# 5_High_Voltage.net
KiCad netlist of a schematic drawn in Altium Designer
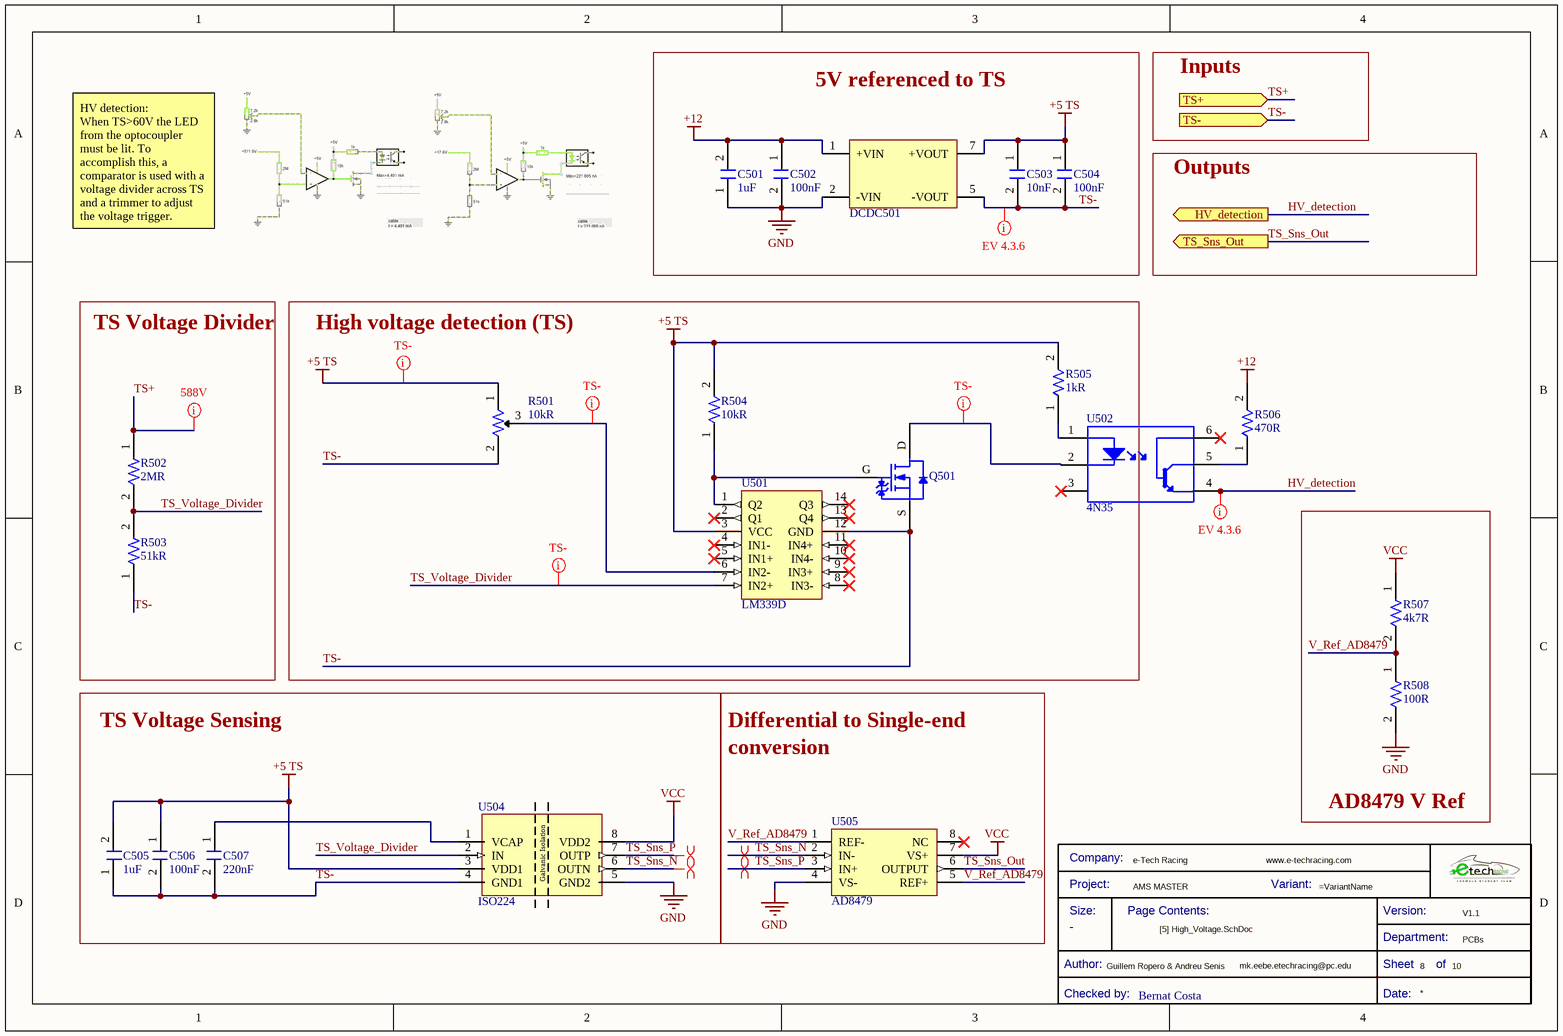
[diagram p0: [5] High_Voltage.SchDoc]

(export (version "E")
  (design (tool "Eeschema 10.0.6"))
  (components
    (comp (ref "C501")
      (value "885012207103")
      (footprint "C0805FNPC-R")
      (fields
        (field (name "TOLERANCE") "10%")
        (field (name "CAPACITANCE") "1uF")
        (field (name ".CREATOR") "GP")
      )
      (libsource (lib "Passives") (part "C1u-50V-0805FNPC-X7R"))
    )
    (comp (ref "C502")
      (value "885012207098")
      (footprint "C0805FNPC-R")
      (description "Cap, 0.1ΜF, 50V, 10%, X7R, 0805")
      (fields
        (field (name "TOLERANCE") "10%")
        (field (name "CAPACITANCE") "100nF")
        (field (name ".CREATOR") "DR")
      )
      (libsource (lib "Passives") (part "C100n-50V-0805FNPC-X7R"))
    )
    (comp (ref "C503")
      (value "885012207092")
      (footprint "C0805FNPC-R")
      (description "Cap, 0.01ΜF, 50V, 10%, X7R, 0805")
      (fields
        (field (name "TOLERANCE") "10%")
        (field (name "CAPACITANCE") "10nF")
        (field (name ".CREATOR") "DR")
      )
      (libsource (lib "Passives") (part "C10n-50V-0805FNPC-X7R"))
    )
    (comp (ref "C504")
      (value "885012207098")
      (footprint "C0805FNPC-R")
      (description "Cap, 0.1ΜF, 50V, 10%, X7R, 0805")
      (fields
        (field (name "TOLERANCE") "10%")
        (field (name "CAPACITANCE") "100nF")
        (field (name ".CREATOR") "DR")
      )
      (libsource (lib "Passives") (part "C100n-50V-0805FNPC-X7R"))
    )
    (comp (ref "C505")
      (value "885012207103")
      (footprint "C0805FNPC-R")
      (fields
        (field (name "TOLERANCE") "10%")
        (field (name "CAPACITANCE") "1uF")
        (field (name ".CREATOR") "GP")
      )
      (libsource (lib "Passives") (part "C1u-50V-0805FNPC-X7R"))
    )
    (comp (ref "C506")
      (value "885012207098")
      (footprint "C0805FNPC-R")
      (description "Cap, 0.1ΜF, 50V, 10%, X7R, 0805")
      (fields
        (field (name "TOLERANCE") "10%")
        (field (name "CAPACITANCE") "100nF")
        (field (name ".CREATOR") "DR")
      )
      (libsource (lib "Passives") (part "C100n-50V-0805FNPC-X7R"))
    )
    (comp (ref "C507")
      (value "885012208058")
      (footprint "C0805FNPC-W")
      (description "Cap Ceramic 0.22uF 50V X5R 10% Pad SMD 0805 85C Low ESR Automotive T/R")
      (fields
        (field (name "MANUFACTURER") "Taiyo Yuden")
        (field (name "MANUFACTURER PART NUMBER") "UMK212BJ224KGHT")
        (field (name "CAPACITANCE") "220nF")
        (field (name ".CREATOR") "DR")
      )
      (libsource (lib "Passives") (part "C0.22u-0805FNPC-X5R"))
    )
    (comp (ref "DCDC501")
      (value "1779405241")
      (footprint "DCDC2W-ISO/1779405X41")
      (description "WPME-FISM Fixed Isolated Module, SIP-7, 10.8-13.2Vin, 5Vout")
      (fields (field (name "MANUFACTURER") "Wurth Elektronik"))
      (libsource (lib "Semiconductor") (part "DCDC-ISO-2W/12V/5V"))
    )
    (comp (ref "Q501")
      (value "SQ2318BES-T1_GE3")
      (footprint "TRT-NCH-3/35-CPH")
      (description "Automotive N-channel 40 V (d-s) 175C Mosfet SOT-23")
      (fields (field (name ".CREATOR") "DO"))
      (libsource (lib "Semiconductor") (part "TRT-NCH-8/40-SQ"))
    )
    (comp (ref "R501")
      (value "3296W-1-103LF")
      (footprint "R10k-VTR")
      (description "Trimmer, Cermet, Rest 10 Kilohms, PCB, 25 Turns, Pwr-Rtg 0.5W, 3296 Series")
      (fields
        (field (name "MANUFACTURER") "Bourns")
        (field (name "TOLERANCE") "10%")
        (field (name "RESISTANCE") "10kR")
        (field (name ".CREATOR") "DO")
      )
      (libsource (lib "Passives") (part "R10k-VTR"))
    )
    (comp (ref "R502")
      (value "R2M-2512FTK")
      (footprint "R2512FTK")
      (description "Current Sense Resistors - SMD 3watts .002ohms 1%")
      (fields
        (field (name "MANUFACTURER") "Vishay Dale")
        (field (name "MANUFACTURER PART NUMBER") "WSLP25122L000FEA")
        (field (name "RESISTANCE") "2MR")
      )
      (libsource (lib "Passives") (part "R2M-2512FTK"))
    )
    (comp (ref "R503")
      (value "CRCW120610K0FKEA")
      (footprint "R1206FTK-W")
      (description "Res Thick Film 1206 51K Ohm 1% 1/4W ±100ppm/°C Molded SMD SMD Punched Carrier T/R")
      (fields
        (field (name "MANUFACTURER") "Panasonic")
        (field (name "MANUFACTURER PART NUMBER") "ERJ-S08F5102V")
        (field (name "RESISTANCE") "51kR")
        (field (name ".CREATOR") "DO")
      )
      (libsource (lib "Passives") (part "R51k-1206FTK"))
    )
    (comp (ref "R504")
      (value "CR0805-JW-103ELF")
      (footprint "R0805FTK")
      (fields
        (field (name "TOLERANCE") "5%")
        (field (name "RESISTANCE") "10kR")
        (field (name ".CREATOR") "DR")
      )
      (libsource (lib "Passives") (part "R10k-0805FTK"))
    )
    (comp (ref "R505")
      (value "CR0805-JW-102ELF")
      (footprint "R0805FTK")
      (description "Res Thick Film 0805 1K Ohm 5% 1/8W ±200ppm/°C Molded SMD SMD Paper Tape on Plastic Reel")
      (fields
        (field (name "TOLERANCE") "5%")
        (field (name "RESISTANCE") "1kR")
        (field (name ".CREATOR") "GP")
      )
      (libsource (lib "Passives") (part "R1k-0805FTK"))
    )
    (comp (ref "R506")
      (value "CR0805-FX-4700GLF")
      (footprint "R0805FTK")
      (description "Res Thick Film 0805 470 Ohm 1% 1/8W ±100ppm/°C Molded SMD SMD Paper Tape on Plastic Reel")
      (fields
        (field (name "TOLERANCE") "1%")
        (field (name "RESISTANCE") "470R")
        (field (name ".CREATOR") "DR")
      )
      (libsource (lib "Passives") (part "R470-0805FTK"))
    )
    (comp (ref "R507")
      (value "CR0805-JW-472ELF")
      (footprint "R0805FTK")
      (description "Res Thick Film 0805 4.7K Ohm 5% 1/8W ±200ppm/°C Molded SMD SMD Paper Tape on Plastic Reel")
      (fields
        (field (name "TOLERANCE") "5%")
        (field (name "RESISTANCE") "4k7R")
        (field (name ".CREATOR") "DR")
      )
      (libsource (lib "Passives") (part "R4.7K-0805FTK"))
    )
    (comp (ref "R508")
      (value "CR0805-FX-1000ELF")
      (footprint "R0805FTK")
      (description "Res Thick Film 0805 100 Ohm 1% 1/8W ±100ppm/°C Molded SMD SMD Paper Tape on Plastic Reel")
      (fields
        (field (name "TOLERANCE") "1%")
        (field (name "RESISTANCE") "100R")
        (field (name ".CREATOR") "DR")
      )
      (libsource (lib "Passives") (part "R100-0805FTK"))
    )
    (comp (ref "U501")
      (value "LM339D")
      (footprint "Array_4_Amp_LM339D")
      (description "Comparator Quad ±18V/36V 14-Pin SOIC Tube")
      (fields
        (field (name "MANUFACTURER") "Texas Instruments")
        (field (name "MANUFACTURER PART NUMBER") "LM339D")
        (field (name ".CREATOR") "DO")
      )
      (libsource (lib "Integrated circuits") (part "Array_4_Amp_LM339D"))
    )
    (comp (ref "U502")
      (value "4N35")
      (footprint "Optocoupler_4N35")
      (description "Optocoupler DC-IN 1-CH Transistor With Base DC-OUT 6-Pin PDIP SMD T/R")
      (fields
        (field (name "MANUFACTURER") "Vishay Lite-On")
        (field (name "MANUFACTURER PART NUMBER") "CNY17-4S-TA1")
        (field (name ".CREATOR") "DO")
      )
      (libsource (lib "Semiconductor") (part "Optocoupler_4N35"))
    )
    (comp (ref "U504")
      (value "ISO224")
      (footprint "SOIC, 8 Pin 1.27 mm, Body 10,90x3,90mm,")
      (libsource (lib "Integrated circuits") (part "ISO224"))
    )
    (comp (ref "U505")
      (value "AD8479")
      (footprint "SOIC127P600X175-8N")
      (description "±600 V common-mode Voltage range, Fixed gain of 1, \r\nWide power supply range of ±2.5 V to ±18 V.")
      (libsource (lib "Integrated circuits") (part "AD8479ARZ-RL"))
    )
  )
  (nets
    (net (code "1") (name "+5 TS") (class "Default")
      (node (ref "C503") (pin "1") (pinfunction "1_1") (pintype "passive"))
      (node (ref "C504") (pin "1") (pinfunction "1_1") (pintype "passive"))
      (node (ref "C505") (pin "2") (pinfunction "2_2") (pintype "passive"))
      (node (ref "C506") (pin "1") (pinfunction "1_1") (pintype "passive"))
      (node (ref "DCDC501") (pin "7") (pinfunction "+VOUT_7") (pintype "passive"))
      (node (ref "R501") (pin "1") (pinfunction "2_1") (pintype "passive"))
      (node (ref "R504") (pin "2") (pinfunction "2_2") (pintype "passive"))
      (node (ref "R505") (pin "2") (pinfunction "2_2") (pintype "passive"))
      (node (ref "U501") (pin "3") (pinfunction "VCC_3") (pintype "power_in"))
      (node (ref "U504") (pin "3") (pinfunction "VDD1_3") (pintype "power_in"))
    )
    (net (code "2") (name "+12") (class "Default")
      (node (ref "C501") (pin "2") (pinfunction "2_2") (pintype "passive"))
      (node (ref "C502") (pin "1") (pinfunction "1_1") (pintype "passive"))
      (node (ref "DCDC501") (pin "1") (pinfunction "+VIN_1") (pintype "passive"))
      (node (ref "R506") (pin "2") (pinfunction "2_2") (pintype "passive"))
    )
    (net (code "3") (name "/HV_detection") (class "Default")
      (node (ref "U502") (pin "4") (pinfunction "E_4") (pintype "passive"))
    )
    (net (code "4") (name "/TS+") (class "Default")
      (node (ref "R502") (pin "1") (pinfunction "1_1") (pintype "passive"))
    )
    (net (code "5") (name "/TS-") (class "Default")
      (node (ref "C503") (pin "2") (pinfunction "2_2") (pintype "passive"))
      (node (ref "C504") (pin "2") (pinfunction "2_2") (pintype "passive"))
      (node (ref "C505") (pin "1") (pinfunction "1_1") (pintype "passive"))
      (node (ref "C506") (pin "2") (pinfunction "2_2") (pintype "passive"))
      (node (ref "C507") (pin "2") (pinfunction "2_2") (pintype "passive"))
      (node (ref "DCDC501") (pin "5") (pinfunction "-VOUT_5") (pintype "passive"))
      (node (ref "Q501") (pin "S") (pinfunction "S_S") (pintype "passive"))
      (node (ref "R501") (pin "2") (pinfunction "2_2") (pintype "passive"))
      (node (ref "R503") (pin "1") (pinfunction "1_1") (pintype "passive"))
      (node (ref "U501") (pin "12") (pinfunction "GND_12") (pintype "power_in"))
      (node (ref "U504") (pin "4") (pinfunction "GND1_4") (pintype "passive"))
    )
    (net (code "6") (name "/TS_Sns_N") (class "Default")
      (node (ref "U504") (pin "6") (pinfunction "OUTN_6") (pintype "output"))
      (node (ref "U505") (pin "2") (pinfunction "IN-_2") (pintype "input"))
    )
    (net (code "7") (name "/TS_Sns_Out") (class "Default")
      (node (ref "U505") (pin "6") (pinfunction "OUTPUT_6") (pintype "output"))
    )
    (net (code "8") (name "/TS_Sns_P") (class "Default")
      (node (ref "U504") (pin "7") (pinfunction "OUTP_7") (pintype "output"))
      (node (ref "U505") (pin "3") (pinfunction "IN+_3") (pintype "input"))
    )
    (net (code "9") (name "/TS_Voltage_Divider") (class "Default")
      (node (ref "R502") (pin "2") (pinfunction "2_2") (pintype "passive"))
      (node (ref "R503") (pin "2") (pinfunction "2_2") (pintype "passive"))
      (node (ref "U501") (pin "7") (pinfunction "IN2+_7") (pintype "input"))
      (node (ref "U504") (pin "2") (pinfunction "IN_2") (pintype "input"))
    )
    (net (code "10") (name "/V_Ref_AD8479") (class "Default")
      (node (ref "R507") (pin "2") (pinfunction "2_2") (pintype "passive"))
      (node (ref "R508") (pin "1") (pinfunction "1_1") (pintype "passive"))
      (node (ref "U505") (pin "1") (pinfunction "REF-_1") (pintype "passive"))
      (node (ref "U505") (pin "5") (pinfunction "REF+_5") (pintype "passive"))
    )
    (net (code "11") (name "GND") (class "Default")
      (node (ref "C501") (pin "1") (pinfunction "1_1") (pintype "passive"))
      (node (ref "C502") (pin "2") (pinfunction "2_2") (pintype "passive"))
      (node (ref "DCDC501") (pin "2") (pinfunction "-VIN_2") (pintype "passive"))
      (node (ref "R508") (pin "2") (pinfunction "2_2") (pintype "passive"))
      (node (ref "U504") (pin "5") (pinfunction "GND2_5") (pintype "power_in"))
      (node (ref "U505") (pin "4") (pinfunction "VS-_4") (pintype "power_in"))
    )
    (net (code "12") (name "Net-(R506-Pad1)") (class "Default")
      (node (ref "R506") (pin "1") (pinfunction "1_1") (pintype "passive"))
      (node (ref "U502") (pin "5") (pinfunction "E_5") (pintype "passive"))
    )
    (net (code "13") (name "Net-(U501-IN2-)") (class "Default")
      (node (ref "R501") (pin "3") (pinfunction "3_3") (pintype "passive"))
      (node (ref "U501") (pin "6") (pinfunction "IN2-_6") (pintype "input"))
    )
    (net (code "14") (name "Net-(U501-Q2)") (class "Default")
      (node (ref "Q501") (pin "G") (pinfunction "G_G") (pintype "passive"))
      (node (ref "R504") (pin "1") (pinfunction "1_1") (pintype "passive"))
      (node (ref "U501") (pin "1") (pinfunction "Q2_1") (pintype "output"))
    )
    (net (code "15") (name "Net-(U502-A)") (class "Default")
      (node (ref "R505") (pin "1") (pinfunction "1_1") (pintype "passive"))
      (node (ref "U502") (pin "1") (pinfunction "A_1") (pintype "passive"))
    )
    (net (code "16") (name "Net-(U502-K)") (class "Default")
      (node (ref "Q501") (pin "D") (pinfunction "D_D") (pintype "passive"))
      (node (ref "U502") (pin "2") (pinfunction "K_2") (pintype "passive"))
    )
    (net (code "17") (name "Net-(U504-VCAP)") (class "Default")
      (node (ref "C507") (pin "1") (pinfunction "1_1") (pintype "passive"))
      (node (ref "U504") (pin "1") (pinfunction "VCAP_1") (pintype "passive"))
    )
    (net (code "18") (name "VCC") (class "Default")
      (node (ref "R507") (pin "1") (pinfunction "1_1") (pintype "passive"))
      (node (ref "U504") (pin "8") (pinfunction "VDD2_8") (pintype "power_in"))
      (node (ref "U505") (pin "7") (pinfunction "VS+_7") (pintype "power_in"))
    )
    (net (code "19") (name "unconnected-(U501-IN1+-Pad5)") (class "Default")
      (node (ref "U501") (pin "5") (pinfunction "IN1+_5") (pintype "input+no_connect"))
    )
    (net (code "20") (name "unconnected-(U501-IN1--Pad4)") (class "Default")
      (node (ref "U501") (pin "4") (pinfunction "IN1-_4") (pintype "input+no_connect"))
    )
    (net (code "21") (name "unconnected-(U501-IN3+-Pad9)") (class "Default")
      (node (ref "U501") (pin "9") (pinfunction "IN3+_9") (pintype "input+no_connect"))
    )
    (net (code "22") (name "unconnected-(U501-IN3--Pad8)") (class "Default")
      (node (ref "U501") (pin "8") (pinfunction "IN3-_8") (pintype "input+no_connect"))
    )
    (net (code "23") (name "unconnected-(U501-IN4+-Pad11)") (class "Default")
      (node (ref "U501") (pin "11") (pinfunction "IN4+_11") (pintype "input+no_connect"))
    )
    (net (code "24") (name "unconnected-(U501-IN4--Pad10)") (class "Default")
      (node (ref "U501") (pin "10") (pinfunction "IN4-_10") (pintype "input+no_connect"))
    )
    (net (code "25") (name "unconnected-(U501-Q1-Pad2)") (class "Default")
      (node (ref "U501") (pin "2") (pinfunction "Q1_2") (pintype "output+no_connect"))
    )
    (net (code "26") (name "unconnected-(U501-Q3-Pad14)") (class "Default")
      (node (ref "U501") (pin "14") (pinfunction "Q3_14") (pintype "output+no_connect"))
    )
    (net (code "27") (name "unconnected-(U501-Q4-Pad13)") (class "Default")
      (node (ref "U501") (pin "13") (pinfunction "Q4_13") (pintype "output+no_connect"))
    )
    (net (code "28") (name "unconnected-(U502-C-Pad3)") (class "Default")
      (node (ref "U502") (pin "3") (pinfunction "C_3") (pintype "passive+no_connect"))
    )
    (net (code "29") (name "unconnected-(U502-E-Pad6)") (class "Default")
      (node (ref "U502") (pin "6") (pinfunction "E_6") (pintype "passive+no_connect"))
    )
    (net (code "30") (name "unconnected-(U505-NC-Pad8)") (class "Default")
      (node (ref "U505") (pin "8") (pinfunction "NC_8") (pintype "passive+no_connect"))
    )
  )
)
